# PGTNXEN_cv_out.net
KiCad netlist of a schematic drawn in EAGLE
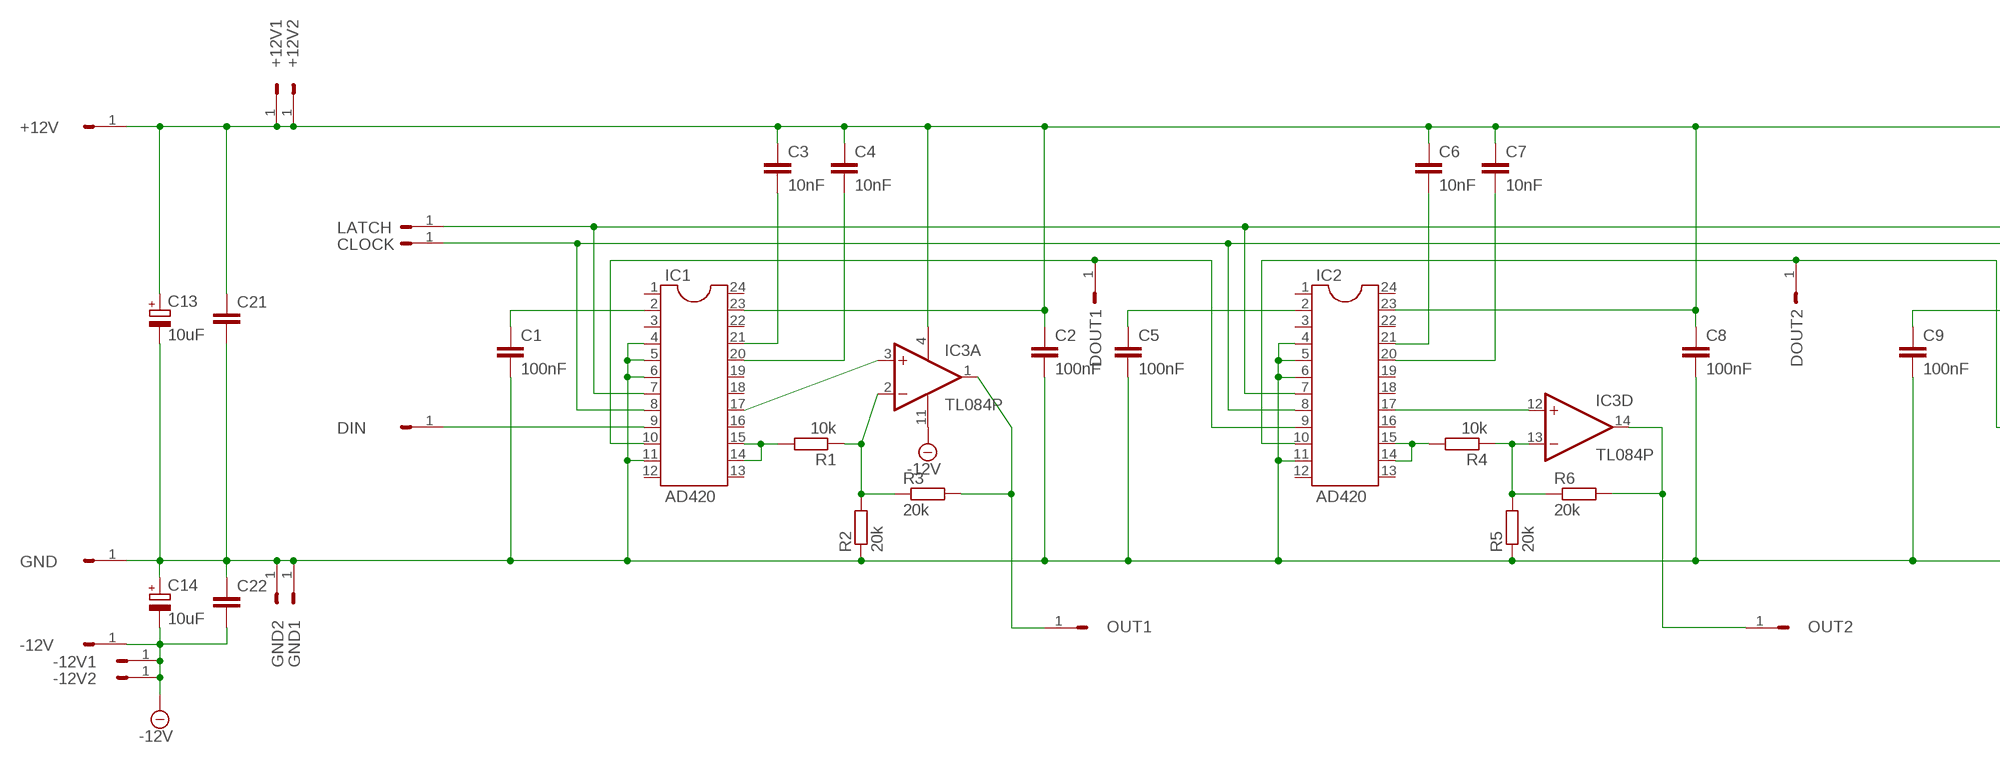
[diagram p0: schematic, sheet 1, part 1 of 2]
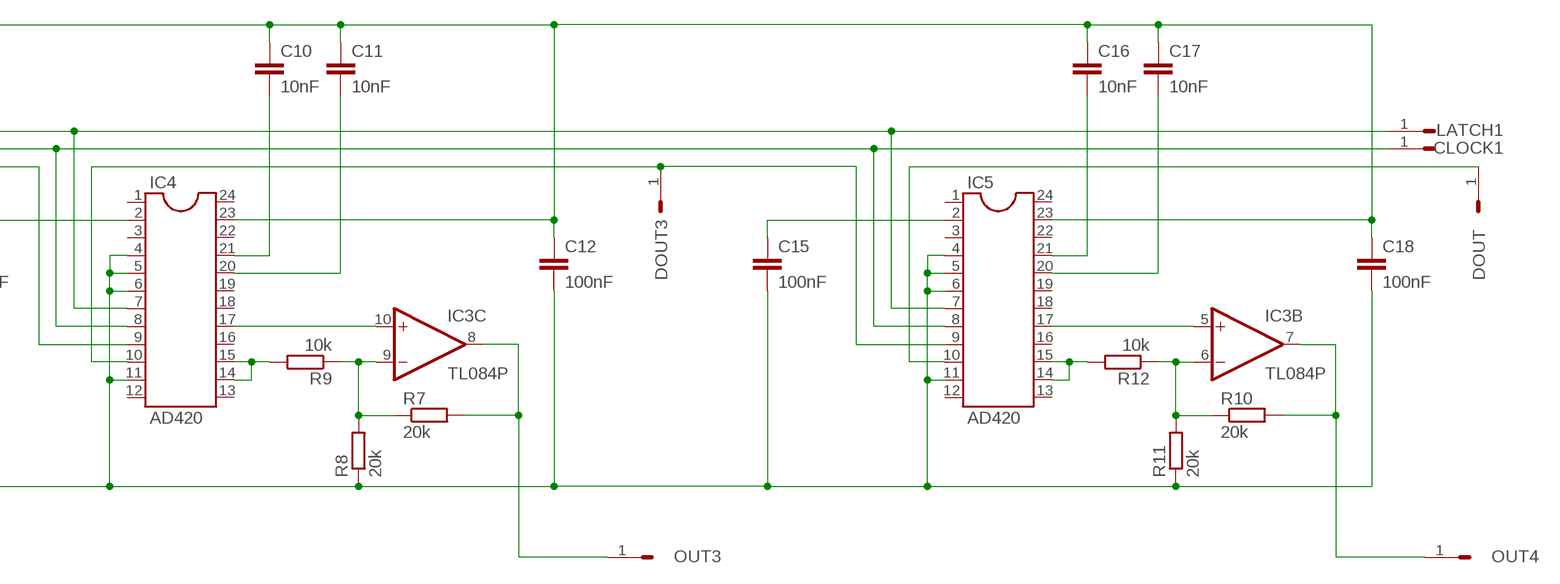
[diagram p1: schematic, sheet 1, part 2 of 2]

(export (version "E")
  (design (tool "Eeschema 10.0.6"))
  (components
    (comp (ref "+12V")
      (value "HEADER/MALE/01")
      (footprint "eagle-import:HEADER_MALE_01")
      (libsource (lib "eagle-import") (part "HEADER/MALE/01"))
    )
    (comp (ref "+12V1")
      (value "HEADER/MALE/01")
      (footprint "eagle-import:HEADER_MALE_01")
      (libsource (lib "eagle-import") (part "HEADER/MALE/01"))
    )
    (comp (ref "+12V2")
      (value "HEADER/MALE/01")
      (footprint "eagle-import:HEADER_MALE_01")
      (libsource (lib "eagle-import") (part "HEADER/MALE/01"))
    )
    (comp (ref "-12V")
      (value "HEADER/MALE/01")
      (footprint "eagle-import:HEADER_MALE_01")
      (libsource (lib "eagle-import") (part "HEADER/MALE/01"))
    )
    (comp (ref "-12V1")
      (value "HEADER/MALE/01")
      (footprint "eagle-import:HEADER_MALE_01")
      (libsource (lib "eagle-import") (part "HEADER/MALE/01"))
    )
    (comp (ref "-12V2")
      (value "HEADER/MALE/01")
      (footprint "eagle-import:HEADER_MALE_01")
      (libsource (lib "eagle-import") (part "HEADER/MALE/01"))
    )
    (comp (ref "C1")
      (value "100nF")
      (footprint "eagle-import:CERAMICDISC_5")
      (libsource (lib "eagle-import") (part "CAPACITORCERAMICDISC/5"))
    )
    (comp (ref "C2")
      (value "100nF")
      (footprint "eagle-import:CERAMICDISC_5")
      (libsource (lib "eagle-import") (part "CAPACITORCERAMICDISC/5"))
    )
    (comp (ref "C3")
      (value "10nF")
      (footprint "eagle-import:CERAMICDISC_5")
      (libsource (lib "eagle-import") (part "CAPACITORCERAMICDISC/5"))
    )
    (comp (ref "C4")
      (value "10nF")
      (footprint "eagle-import:CERAMICDISC_5")
      (libsource (lib "eagle-import") (part "CAPACITORCERAMICDISC/5"))
    )
    (comp (ref "C5")
      (value "100nF")
      (footprint "eagle-import:CERAMICDISC_5")
      (libsource (lib "eagle-import") (part "CAPACITORCERAMICDISC/5"))
    )
    (comp (ref "C6")
      (value "10nF")
      (footprint "eagle-import:CERAMICDISC_5")
      (libsource (lib "eagle-import") (part "CAPACITORCERAMICDISC/5"))
    )
    (comp (ref "C7")
      (value "10nF")
      (footprint "eagle-import:CERAMICDISC_5")
      (libsource (lib "eagle-import") (part "CAPACITORCERAMICDISC/5"))
    )
    (comp (ref "C8")
      (value "100nF")
      (footprint "eagle-import:CERAMICDISC_5")
      (libsource (lib "eagle-import") (part "CAPACITORCERAMICDISC/5"))
    )
    (comp (ref "C9")
      (value "100nF")
      (footprint "eagle-import:CERAMICDISC_5")
      (libsource (lib "eagle-import") (part "CAPACITORCERAMICDISC/5"))
    )
    (comp (ref "C10")
      (value "10nF")
      (footprint "eagle-import:CERAMICDISC_5")
      (libsource (lib "eagle-import") (part "CAPACITORCERAMICDISC/5"))
    )
    (comp (ref "C11")
      (value "10nF")
      (footprint "eagle-import:CERAMICDISC_5")
      (libsource (lib "eagle-import") (part "CAPACITORCERAMICDISC/5"))
    )
    (comp (ref "C12")
      (value "100nF")
      (footprint "eagle-import:CERAMICDISC_5")
      (libsource (lib "eagle-import") (part "CAPACITORCERAMICDISC/5"))
    )
    (comp (ref "C13")
      (value "10uF")
      (footprint "eagle-import:E2,5-6")
      (libsource (lib "eagle-import") (part "CAPACITOR/POLARIZEDE2.5-6"))
    )
    (comp (ref "C14")
      (value "10uF")
      (footprint "eagle-import:E2,5-6")
      (libsource (lib "eagle-import") (part "CAPACITOR/POLARIZEDE2.5-6"))
    )
    (comp (ref "C15")
      (value "100nF")
      (footprint "eagle-import:CERAMICDISC_5")
      (libsource (lib "eagle-import") (part "CAPACITORCERAMICDISC/5"))
    )
    (comp (ref "C16")
      (value "10nF")
      (footprint "eagle-import:CERAMICDISC_5")
      (libsource (lib "eagle-import") (part "CAPACITORCERAMICDISC/5"))
    )
    (comp (ref "C17")
      (value "10nF")
      (footprint "eagle-import:CERAMICDISC_5")
      (libsource (lib "eagle-import") (part "CAPACITORCERAMICDISC/5"))
    )
    (comp (ref "C18")
      (value "100nF")
      (footprint "eagle-import:CERAMICDISC_5")
      (libsource (lib "eagle-import") (part "CAPACITORCERAMICDISC/5"))
    )
    (comp (ref "C21")
      (value "CAPACITORCERAMICDISC/5")
      (footprint "eagle-import:CERAMICDISC_5")
      (libsource (lib "eagle-import") (part "CAPACITORCERAMICDISC/5"))
    )
    (comp (ref "C22")
      (value "CAPACITORCERAMICDISC/5")
      (footprint "eagle-import:CERAMICDISC_5")
      (libsource (lib "eagle-import") (part "CAPACITORCERAMICDISC/5"))
    )
    (comp (ref "CLOCK")
      (value "HEADER/MALE/01")
      (footprint "eagle-import:HEADER_MALE_01")
      (libsource (lib "eagle-import") (part "HEADER/MALE/01"))
    )
    (comp (ref "CLOCK1")
      (value "HEADER/MALE/01")
      (footprint "eagle-import:HEADER_MALE_01")
      (libsource (lib "eagle-import") (part "HEADER/MALE/01"))
    )
    (comp (ref "DIN")
      (value "HEADER/MALE/01")
      (footprint "eagle-import:HEADER_MALE_01")
      (libsource (lib "eagle-import") (part "HEADER/MALE/01"))
    )
    (comp (ref "DOUT")
      (value "HEADER/MALE/01")
      (footprint "eagle-import:HEADER_MALE_01")
      (libsource (lib "eagle-import") (part "HEADER/MALE/01"))
    )
    (comp (ref "DOUT1")
      (value "HEADER/MALE/01")
      (footprint "eagle-import:HEADER_MALE_01")
      (libsource (lib "eagle-import") (part "HEADER/MALE/01"))
    )
    (comp (ref "DOUT2")
      (value "HEADER/MALE/01")
      (footprint "eagle-import:HEADER_MALE_01")
      (libsource (lib "eagle-import") (part "HEADER/MALE/01"))
    )
    (comp (ref "DOUT3")
      (value "HEADER/MALE/01")
      (footprint "eagle-import:HEADER_MALE_01")
      (libsource (lib "eagle-import") (part "HEADER/MALE/01"))
    )
    (comp (ref "GND")
      (value "HEADER/MALE/01")
      (footprint "eagle-import:HEADER_MALE_01")
      (libsource (lib "eagle-import") (part "HEADER/MALE/01"))
    )
    (comp (ref "GND1")
      (value "HEADER/MALE/01")
      (footprint "eagle-import:HEADER_MALE_01")
      (libsource (lib "eagle-import") (part "HEADER/MALE/01"))
    )
    (comp (ref "GND2")
      (value "HEADER/MALE/01")
      (footprint "eagle-import:HEADER_MALE_01")
      (libsource (lib "eagle-import") (part "HEADER/MALE/01"))
    )
    (comp (ref "IC1")
      (value "AD420")
      (footprint "eagle-import:DIL24-3")
      (libsource (lib "eagle-import") (part "DIL24-3"))
    )
    (comp (ref "IC2")
      (value "AD420")
      (footprint "eagle-import:DIL24-3")
      (libsource (lib "eagle-import") (part "DIL24-3"))
    )
    (comp (ref "IC3")
      (value "TL084P")
      (footprint "eagle-import:DIL14")
      (libsource (lib "eagle-import") (part "TL084P"))
    )
    (comp (ref "IC4")
      (value "AD420")
      (footprint "eagle-import:DIL24-3")
      (libsource (lib "eagle-import") (part "DIL24-3"))
    )
    (comp (ref "IC5")
      (value "AD420")
      (footprint "eagle-import:DIL24-3")
      (libsource (lib "eagle-import") (part "DIL24-3"))
    )
    (comp (ref "LATCH")
      (value "HEADER/MALE/01")
      (footprint "eagle-import:HEADER_MALE_01")
      (libsource (lib "eagle-import") (part "HEADER/MALE/01"))
    )
    (comp (ref "LATCH1")
      (value "HEADER/MALE/01")
      (footprint "eagle-import:HEADER_MALE_01")
      (libsource (lib "eagle-import") (part "HEADER/MALE/01"))
    )
    (comp (ref "OUT1")
      (value "HEADER/MALE/01")
      (footprint "eagle-import:HEADER_MALE_01")
      (libsource (lib "eagle-import") (part "HEADER/MALE/01"))
    )
    (comp (ref "OUT2")
      (value "HEADER/MALE/01")
      (footprint "eagle-import:HEADER_MALE_01")
      (libsource (lib "eagle-import") (part "HEADER/MALE/01"))
    )
    (comp (ref "OUT3")
      (value "HEADER/MALE/01")
      (footprint "eagle-import:HEADER_MALE_01")
      (libsource (lib "eagle-import") (part "HEADER/MALE/01"))
    )
    (comp (ref "OUT4")
      (value "HEADER/MALE/01")
      (footprint "eagle-import:HEADER_MALE_01")
      (libsource (lib "eagle-import") (part "HEADER/MALE/01"))
    )
    (comp (ref "R1")
      (value "10k")
      (footprint "eagle-import:0204_7")
      (libsource (lib "eagle-import") (part "R-EU_0204/7"))
    )
    (comp (ref "R2")
      (value "20k")
      (footprint "eagle-import:0204_7")
      (libsource (lib "eagle-import") (part "R-EU_0204/7"))
    )
    (comp (ref "R3")
      (value "20k")
      (footprint "eagle-import:0204_7")
      (libsource (lib "eagle-import") (part "R-EU_0204/7"))
    )
    (comp (ref "R4")
      (value "10k")
      (footprint "eagle-import:0204_7")
      (libsource (lib "eagle-import") (part "R-EU_0204/7"))
    )
    (comp (ref "R5")
      (value "20k")
      (footprint "eagle-import:0204_7")
      (libsource (lib "eagle-import") (part "R-EU_0204/7"))
    )
    (comp (ref "R6")
      (value "20k")
      (footprint "eagle-import:0204_7")
      (libsource (lib "eagle-import") (part "R-EU_0204/7"))
    )
    (comp (ref "R7")
      (value "20k")
      (footprint "eagle-import:0204_7")
      (libsource (lib "eagle-import") (part "R-EU_0204/7"))
    )
    (comp (ref "R8")
      (value "20k")
      (footprint "eagle-import:0204_7")
      (libsource (lib "eagle-import") (part "R-EU_0204/7"))
    )
    (comp (ref "R9")
      (value "10k")
      (footprint "eagle-import:0204_7")
      (libsource (lib "eagle-import") (part "R-EU_0204/7"))
    )
    (comp (ref "R10")
      (value "20k")
      (footprint "eagle-import:0204_7")
      (libsource (lib "eagle-import") (part "R-EU_0204/7"))
    )
    (comp (ref "R11")
      (value "20k")
      (footprint "eagle-import:0204_7")
      (libsource (lib "eagle-import") (part "R-EU_0204/7"))
    )
    (comp (ref "R12")
      (value "10k")
      (footprint "eagle-import:0204_7")
      (libsource (lib "eagle-import") (part "R-EU_0204/7"))
    )
  )
  (nets
    (net (code "1") (name "-12V") (class "Default")
      (node (ref "-12V") (pin "1") (pinfunction "3_1") (pintype "passive"))
      (node (ref "-12V1") (pin "1") (pinfunction "3_1") (pintype "passive"))
      (node (ref "-12V2") (pin "1") (pinfunction "3_1") (pintype "passive"))
      (node (ref "C14") (pin "-") (pinfunction "-_-") (pintype "passive"))
      (node (ref "C22") (pin "2") (pinfunction "2_2") (pintype "passive"))
      (node (ref "IC3") (pin "11") (pinfunction "V-_11") (pintype "power_in"))
    )
    (net (code "2") (name "Net-(+12V-3)") (class "Default")
      (node (ref "+12V") (pin "1") (pinfunction "3_1") (pintype "passive"))
      (node (ref "+12V1") (pin "1") (pinfunction "3_1") (pintype "passive"))
      (node (ref "+12V2") (pin "1") (pinfunction "3_1") (pintype "passive"))
      (node (ref "C10") (pin "1") (pinfunction "1_1") (pintype "passive"))
      (node (ref "C11") (pin "1") (pinfunction "1_1") (pintype "passive"))
      (node (ref "C12") (pin "1") (pinfunction "1_1") (pintype "passive"))
      (node (ref "C13") (pin "+") (pinfunction "+_+") (pintype "passive"))
      (node (ref "C16") (pin "1") (pinfunction "1_1") (pintype "passive"))
      (node (ref "C17") (pin "1") (pinfunction "1_1") (pintype "passive"))
      (node (ref "C18") (pin "1") (pinfunction "1_1") (pintype "passive"))
      (node (ref "C2") (pin "1") (pinfunction "1_1") (pintype "passive"))
      (node (ref "C21") (pin "1") (pinfunction "1_1") (pintype "passive"))
      (node (ref "C3") (pin "1") (pinfunction "1_1") (pintype "passive"))
      (node (ref "C4") (pin "1") (pinfunction "1_1") (pintype "passive"))
      (node (ref "C6") (pin "1") (pinfunction "1_1") (pintype "passive"))
      (node (ref "C7") (pin "1") (pinfunction "1_1") (pintype "passive"))
      (node (ref "C8") (pin "1") (pinfunction "1_1") (pintype "passive"))
      (node (ref "IC1") (pin "23") (pinfunction "23_23") (pintype "passive"))
      (node (ref "IC2") (pin "23") (pinfunction "23_23") (pintype "passive"))
      (node (ref "IC3") (pin "4") (pinfunction "V+_4") (pintype "power_in"))
      (node (ref "IC4") (pin "23") (pinfunction "23_23") (pintype "passive"))
      (node (ref "IC5") (pin "23") (pinfunction "23_23") (pintype "passive"))
    )
    (net (code "3") (name "Net-(C1-Pad1)") (class "Default")
      (node (ref "C1") (pin "1") (pinfunction "1_1") (pintype "passive"))
      (node (ref "IC1") (pin "2") (pinfunction "2_2") (pintype "passive"))
    )
    (net (code "4") (name "Net-(C3-Pad2)") (class "Default")
      (node (ref "C3") (pin "2") (pinfunction "2_2") (pintype "passive"))
      (node (ref "IC1") (pin "21") (pinfunction "21_21") (pintype "passive"))
    )
    (net (code "5") (name "Net-(C4-Pad2)") (class "Default")
      (node (ref "C4") (pin "2") (pinfunction "2_2") (pintype "passive"))
      (node (ref "IC1") (pin "20") (pinfunction "20_20") (pintype "passive"))
    )
    (net (code "6") (name "Net-(C5-Pad1)") (class "Default")
      (node (ref "C5") (pin "1") (pinfunction "1_1") (pintype "passive"))
      (node (ref "IC2") (pin "2") (pinfunction "2_2") (pintype "passive"))
    )
    (net (code "7") (name "Net-(C6-Pad2)") (class "Default")
      (node (ref "C6") (pin "2") (pinfunction "2_2") (pintype "passive"))
      (node (ref "IC2") (pin "21") (pinfunction "21_21") (pintype "passive"))
    )
    (net (code "8") (name "Net-(C7-Pad2)") (class "Default")
      (node (ref "C7") (pin "2") (pinfunction "2_2") (pintype "passive"))
      (node (ref "IC2") (pin "20") (pinfunction "20_20") (pintype "passive"))
    )
    (net (code "9") (name "Net-(C9-Pad1)") (class "Default")
      (node (ref "C9") (pin "1") (pinfunction "1_1") (pintype "passive"))
      (node (ref "IC4") (pin "2") (pinfunction "2_2") (pintype "passive"))
    )
    (net (code "10") (name "Net-(C10-Pad2)") (class "Default")
      (node (ref "C10") (pin "2") (pinfunction "2_2") (pintype "passive"))
      (node (ref "IC4") (pin "21") (pinfunction "21_21") (pintype "passive"))
    )
    (net (code "11") (name "Net-(C11-Pad2)") (class "Default")
      (node (ref "C11") (pin "2") (pinfunction "2_2") (pintype "passive"))
      (node (ref "IC4") (pin "20") (pinfunction "20_20") (pintype "passive"))
    )
    (net (code "12") (name "Net-(C15-Pad1)") (class "Default")
      (node (ref "C15") (pin "1") (pinfunction "1_1") (pintype "passive"))
      (node (ref "IC5") (pin "2") (pinfunction "2_2") (pintype "passive"))
    )
    (net (code "13") (name "Net-(C16-Pad2)") (class "Default")
      (node (ref "C16") (pin "2") (pinfunction "2_2") (pintype "passive"))
      (node (ref "IC5") (pin "21") (pinfunction "21_21") (pintype "passive"))
    )
    (net (code "14") (name "Net-(C17-Pad2)") (class "Default")
      (node (ref "C17") (pin "2") (pinfunction "2_2") (pintype "passive"))
      (node (ref "IC5") (pin "20") (pinfunction "20_20") (pintype "passive"))
    )
    (net (code "15") (name "Net-(CLOCK-3)") (class "Default")
      (node (ref "CLOCK") (pin "1") (pinfunction "3_1") (pintype "passive"))
      (node (ref "CLOCK1") (pin "1") (pinfunction "3_1") (pintype "passive"))
      (node (ref "IC1") (pin "8") (pinfunction "8_8") (pintype "passive"))
      (node (ref "IC2") (pin "8") (pinfunction "8_8") (pintype "passive"))
      (node (ref "IC4") (pin "8") (pinfunction "8_8") (pintype "passive"))
      (node (ref "IC5") (pin "8") (pinfunction "8_8") (pintype "passive"))
    )
    (net (code "16") (name "Net-(DIN-3)") (class "Default")
      (node (ref "DIN") (pin "1") (pinfunction "3_1") (pintype "passive"))
      (node (ref "IC1") (pin "9") (pinfunction "9_9") (pintype "passive"))
    )
    (net (code "17") (name "Net-(DOUT-3)") (class "Default")
      (node (ref "DOUT") (pin "1") (pinfunction "3_1") (pintype "passive"))
      (node (ref "IC5") (pin "10") (pinfunction "10_10") (pintype "passive"))
    )
    (net (code "18") (name "Net-(DOUT1-3)") (class "Default")
      (node (ref "DOUT1") (pin "1") (pinfunction "3_1") (pintype "passive"))
      (node (ref "IC1") (pin "10") (pinfunction "10_10") (pintype "passive"))
      (node (ref "IC2") (pin "9") (pinfunction "9_9") (pintype "passive"))
    )
    (net (code "19") (name "Net-(DOUT2-3)") (class "Default")
      (node (ref "DOUT2") (pin "1") (pinfunction "3_1") (pintype "passive"))
      (node (ref "IC2") (pin "10") (pinfunction "10_10") (pintype "passive"))
      (node (ref "IC4") (pin "9") (pinfunction "9_9") (pintype "passive"))
    )
    (net (code "20") (name "Net-(DOUT3-3)") (class "Default")
      (node (ref "DOUT3") (pin "1") (pinfunction "3_1") (pintype "passive"))
      (node (ref "IC4") (pin "10") (pinfunction "10_10") (pintype "passive"))
      (node (ref "IC5") (pin "9") (pinfunction "9_9") (pintype "passive"))
    )
    (net (code "21") (name "Net-(GND-3)") (class "Default")
      (node (ref "C1") (pin "2") (pinfunction "2_2") (pintype "passive"))
      (node (ref "C12") (pin "2") (pinfunction "2_2") (pintype "passive"))
      (node (ref "C13") (pin "-") (pinfunction "-_-") (pintype "passive"))
      (node (ref "C14") (pin "+") (pinfunction "+_+") (pintype "passive"))
      (node (ref "C15") (pin "2") (pinfunction "2_2") (pintype "passive"))
      (node (ref "C18") (pin "2") (pinfunction "2_2") (pintype "passive"))
      (node (ref "C2") (pin "2") (pinfunction "2_2") (pintype "passive"))
      (node (ref "C21") (pin "2") (pinfunction "2_2") (pintype "passive"))
      (node (ref "C22") (pin "1") (pinfunction "1_1") (pintype "passive"))
      (node (ref "C5") (pin "2") (pinfunction "2_2") (pintype "passive"))
      (node (ref "C8") (pin "2") (pinfunction "2_2") (pintype "passive"))
      (node (ref "C9") (pin "2") (pinfunction "2_2") (pintype "passive"))
      (node (ref "GND") (pin "1") (pinfunction "3_1") (pintype "passive"))
      (node (ref "GND1") (pin "1") (pinfunction "3_1") (pintype "passive"))
      (node (ref "GND2") (pin "1") (pinfunction "3_1") (pintype "passive"))
      (node (ref "IC1") (pin "11") (pinfunction "11_11") (pintype "passive"))
      (node (ref "IC1") (pin "4") (pinfunction "4_4") (pintype "passive"))
      (node (ref "IC1") (pin "5") (pinfunction "5_5") (pintype "passive"))
      (node (ref "IC1") (pin "6") (pinfunction "6_6") (pintype "passive"))
      (node (ref "IC2") (pin "11") (pinfunction "11_11") (pintype "passive"))
      (node (ref "IC2") (pin "4") (pinfunction "4_4") (pintype "passive"))
      (node (ref "IC2") (pin "5") (pinfunction "5_5") (pintype "passive"))
      (node (ref "IC2") (pin "6") (pinfunction "6_6") (pintype "passive"))
      (node (ref "IC4") (pin "11") (pinfunction "11_11") (pintype "passive"))
      (node (ref "IC4") (pin "4") (pinfunction "4_4") (pintype "passive"))
      (node (ref "IC4") (pin "5") (pinfunction "5_5") (pintype "passive"))
      (node (ref "IC4") (pin "6") (pinfunction "6_6") (pintype "passive"))
      (node (ref "IC5") (pin "11") (pinfunction "11_11") (pintype "passive"))
      (node (ref "IC5") (pin "4") (pinfunction "4_4") (pintype "passive"))
      (node (ref "IC5") (pin "5") (pinfunction "5_5") (pintype "passive"))
      (node (ref "IC5") (pin "6") (pinfunction "6_6") (pintype "passive"))
      (node (ref "R11") (pin "1") (pinfunction "1_1") (pintype "passive"))
      (node (ref "R2") (pin "1") (pinfunction "1_1") (pintype "passive"))
      (node (ref "R5") (pin "1") (pinfunction "1_1") (pintype "passive"))
      (node (ref "R8") (pin "1") (pinfunction "1_1") (pintype "passive"))
    )
    (net (code "22") (name "Net-(IC1-Pad14)") (class "Default")
      (node (ref "IC1") (pin "14") (pinfunction "14_14") (pintype "passive"))
      (node (ref "IC1") (pin "15") (pinfunction "15_15") (pintype "passive"))
      (node (ref "R1") (pin "2") (pinfunction "2_2") (pintype "passive"))
    )
    (net (code "23") (name "Net-(IC2-Pad14)") (class "Default")
      (node (ref "IC2") (pin "14") (pinfunction "14_14") (pintype "passive"))
      (node (ref "IC2") (pin "15") (pinfunction "15_15") (pintype "passive"))
      (node (ref "R4") (pin "2") (pinfunction "2_2") (pintype "passive"))
    )
    (net (code "24") (name "Net-(IC3A-+IN)") (class "Default")
      (node (ref "IC1") (pin "17") (pinfunction "17_17") (pintype "passive"))
      (node (ref "IC3") (pin "3") (pinfunction "+IN_3") (pintype "input"))
    )
    (net (code "25") (name "Net-(IC3A--IN)") (class "Default")
      (node (ref "IC3") (pin "2") (pinfunction "-IN_2") (pintype "input"))
      (node (ref "R1") (pin "1") (pinfunction "1_1") (pintype "passive"))
      (node (ref "R2") (pin "2") (pinfunction "2_2") (pintype "passive"))
      (node (ref "R3") (pin "1") (pinfunction "1_1") (pintype "passive"))
    )
    (net (code "26") (name "Net-(IC3A-OUT)") (class "Default")
      (node (ref "IC3") (pin "1") (pinfunction "OUT_1") (pintype "output"))
      (node (ref "OUT1") (pin "1") (pinfunction "3_1") (pintype "passive"))
      (node (ref "R3") (pin "2") (pinfunction "2_2") (pintype "passive"))
    )
    (net (code "27") (name "Net-(IC3B-+IN)") (class "Default")
      (node (ref "IC3") (pin "5") (pinfunction "+IN_5") (pintype "input"))
      (node (ref "IC5") (pin "17") (pinfunction "17_17") (pintype "passive"))
    )
    (net (code "28") (name "Net-(IC3B--IN)") (class "Default")
      (node (ref "IC3") (pin "6") (pinfunction "-IN_6") (pintype "input"))
      (node (ref "R10") (pin "1") (pinfunction "1_1") (pintype "passive"))
      (node (ref "R11") (pin "2") (pinfunction "2_2") (pintype "passive"))
      (node (ref "R12") (pin "1") (pinfunction "1_1") (pintype "passive"))
    )
    (net (code "29") (name "Net-(IC3B-OUT)") (class "Default")
      (node (ref "IC3") (pin "7") (pinfunction "OUT_7") (pintype "output"))
      (node (ref "OUT4") (pin "1") (pinfunction "3_1") (pintype "passive"))
      (node (ref "R10") (pin "2") (pinfunction "2_2") (pintype "passive"))
    )
    (net (code "30") (name "Net-(IC3C-+IN)") (class "Default")
      (node (ref "IC3") (pin "10") (pinfunction "+IN_10") (pintype "input"))
      (node (ref "IC4") (pin "17") (pinfunction "17_17") (pintype "passive"))
    )
    (net (code "31") (name "Net-(IC3C--IN)") (class "Default")
      (node (ref "IC3") (pin "9") (pinfunction "-IN_9") (pintype "input"))
      (node (ref "R7") (pin "1") (pinfunction "1_1") (pintype "passive"))
      (node (ref "R8") (pin "2") (pinfunction "2_2") (pintype "passive"))
      (node (ref "R9") (pin "1") (pinfunction "1_1") (pintype "passive"))
    )
    (net (code "32") (name "Net-(IC3C-OUT)") (class "Default")
      (node (ref "IC3") (pin "8") (pinfunction "OUT_8") (pintype "output"))
      (node (ref "OUT3") (pin "1") (pinfunction "3_1") (pintype "passive"))
      (node (ref "R7") (pin "2") (pinfunction "2_2") (pintype "passive"))
    )
    (net (code "33") (name "Net-(IC3D-+IN)") (class "Default")
      (node (ref "IC2") (pin "17") (pinfunction "17_17") (pintype "passive"))
      (node (ref "IC3") (pin "12") (pinfunction "+IN_12") (pintype "input"))
    )
    (net (code "34") (name "Net-(IC3D--IN)") (class "Default")
      (node (ref "IC3") (pin "13") (pinfunction "-IN_13") (pintype "input"))
      (node (ref "R4") (pin "1") (pinfunction "1_1") (pintype "passive"))
      (node (ref "R5") (pin "2") (pinfunction "2_2") (pintype "passive"))
      (node (ref "R6") (pin "1") (pinfunction "1_1") (pintype "passive"))
    )
    (net (code "35") (name "Net-(IC3D-OUT)") (class "Default")
      (node (ref "IC3") (pin "14") (pinfunction "OUT_14") (pintype "output"))
      (node (ref "OUT2") (pin "1") (pinfunction "3_1") (pintype "passive"))
      (node (ref "R6") (pin "2") (pinfunction "2_2") (pintype "passive"))
    )
    (net (code "36") (name "Net-(IC4-Pad14)") (class "Default")
      (node (ref "IC4") (pin "14") (pinfunction "14_14") (pintype "passive"))
      (node (ref "IC4") (pin "15") (pinfunction "15_15") (pintype "passive"))
      (node (ref "R9") (pin "2") (pinfunction "2_2") (pintype "passive"))
    )
    (net (code "37") (name "Net-(IC5-Pad14)") (class "Default")
      (node (ref "IC5") (pin "14") (pinfunction "14_14") (pintype "passive"))
      (node (ref "IC5") (pin "15") (pinfunction "15_15") (pintype "passive"))
      (node (ref "R12") (pin "2") (pinfunction "2_2") (pintype "passive"))
    )
    (net (code "38") (name "Net-(LATCH-3)") (class "Default")
      (node (ref "IC1") (pin "7") (pinfunction "7_7") (pintype "passive"))
      (node (ref "IC2") (pin "7") (pinfunction "7_7") (pintype "passive"))
      (node (ref "IC4") (pin "7") (pinfunction "7_7") (pintype "passive"))
      (node (ref "IC5") (pin "7") (pinfunction "7_7") (pintype "passive"))
      (node (ref "LATCH") (pin "1") (pinfunction "3_1") (pintype "passive"))
      (node (ref "LATCH1") (pin "1") (pinfunction "3_1") (pintype "passive"))
    )
    (net (code "39") (name "unconnected-(IC1-Pad1)") (class "Default")
      (node (ref "IC1") (pin "1") (pinfunction "1_1") (pintype "passive"))
    )
    (net (code "40") (name "unconnected-(IC1-Pad3)") (class "Default")
      (node (ref "IC1") (pin "3") (pinfunction "3_3") (pintype "passive"))
    )
    (net (code "41") (name "unconnected-(IC1-Pad12)") (class "Default")
      (node (ref "IC1") (pin "12") (pinfunction "12_12") (pintype "passive"))
    )
    (net (code "42") (name "unconnected-(IC1-Pad13)") (class "Default")
      (node (ref "IC1") (pin "13") (pinfunction "13_13") (pintype "passive"))
    )
    (net (code "43") (name "unconnected-(IC1-Pad16)") (class "Default")
      (node (ref "IC1") (pin "16") (pinfunction "16_16") (pintype "passive"))
    )
    (net (code "44") (name "unconnected-(IC1-Pad18)") (class "Default")
      (node (ref "IC1") (pin "18") (pinfunction "18_18") (pintype "passive"))
    )
    (net (code "45") (name "unconnected-(IC1-Pad19)") (class "Default")
      (node (ref "IC1") (pin "19") (pinfunction "19_19") (pintype "passive"))
    )
    (net (code "46") (name "unconnected-(IC1-Pad22)") (class "Default")
      (node (ref "IC1") (pin "22") (pinfunction "22_22") (pintype "passive"))
    )
    (net (code "47") (name "unconnected-(IC1-Pad24)") (class "Default")
      (node (ref "IC1") (pin "24") (pinfunction "24_24") (pintype "passive"))
    )
    (net (code "48") (name "unconnected-(IC2-Pad1)") (class "Default")
      (node (ref "IC2") (pin "1") (pinfunction "1_1") (pintype "passive"))
    )
    (net (code "49") (name "unconnected-(IC2-Pad3)") (class "Default")
      (node (ref "IC2") (pin "3") (pinfunction "3_3") (pintype "passive"))
    )
    (net (code "50") (name "unconnected-(IC2-Pad12)") (class "Default")
      (node (ref "IC2") (pin "12") (pinfunction "12_12") (pintype "passive"))
    )
    (net (code "51") (name "unconnected-(IC2-Pad13)") (class "Default")
      (node (ref "IC2") (pin "13") (pinfunction "13_13") (pintype "passive"))
    )
    (net (code "52") (name "unconnected-(IC2-Pad16)") (class "Default")
      (node (ref "IC2") (pin "16") (pinfunction "16_16") (pintype "passive"))
    )
    (net (code "53") (name "unconnected-(IC2-Pad18)") (class "Default")
      (node (ref "IC2") (pin "18") (pinfunction "18_18") (pintype "passive"))
    )
    (net (code "54") (name "unconnected-(IC2-Pad19)") (class "Default")
      (node (ref "IC2") (pin "19") (pinfunction "19_19") (pintype "passive"))
    )
    (net (code "55") (name "unconnected-(IC2-Pad22)") (class "Default")
      (node (ref "IC2") (pin "22") (pinfunction "22_22") (pintype "passive"))
    )
    (net (code "56") (name "unconnected-(IC2-Pad24)") (class "Default")
      (node (ref "IC2") (pin "24") (pinfunction "24_24") (pintype "passive"))
    )
    (net (code "57") (name "unconnected-(IC4-Pad1)") (class "Default")
      (node (ref "IC4") (pin "1") (pinfunction "1_1") (pintype "passive"))
    )
    (net (code "58") (name "unconnected-(IC4-Pad3)") (class "Default")
      (node (ref "IC4") (pin "3") (pinfunction "3_3") (pintype "passive"))
    )
    (net (code "59") (name "unconnected-(IC4-Pad12)") (class "Default")
      (node (ref "IC4") (pin "12") (pinfunction "12_12") (pintype "passive"))
    )
    (net (code "60") (name "unconnected-(IC4-Pad13)") (class "Default")
      (node (ref "IC4") (pin "13") (pinfunction "13_13") (pintype "passive"))
    )
    (net (code "61") (name "unconnected-(IC4-Pad16)") (class "Default")
      (node (ref "IC4") (pin "16") (pinfunction "16_16") (pintype "passive"))
    )
    (net (code "62") (name "unconnected-(IC4-Pad18)") (class "Default")
      (node (ref "IC4") (pin "18") (pinfunction "18_18") (pintype "passive"))
    )
    (net (code "63") (name "unconnected-(IC4-Pad19)") (class "Default")
      (node (ref "IC4") (pin "19") (pinfunction "19_19") (pintype "passive"))
    )
    (net (code "64") (name "unconnected-(IC4-Pad22)") (class "Default")
      (node (ref "IC4") (pin "22") (pinfunction "22_22") (pintype "passive"))
    )
    (net (code "65") (name "unconnected-(IC4-Pad24)") (class "Default")
      (node (ref "IC4") (pin "24") (pinfunction "24_24") (pintype "passive"))
    )
    (net (code "66") (name "unconnected-(IC5-Pad1)") (class "Default")
      (node (ref "IC5") (pin "1") (pinfunction "1_1") (pintype "passive"))
    )
    (net (code "67") (name "unconnected-(IC5-Pad3)") (class "Default")
      (node (ref "IC5") (pin "3") (pinfunction "3_3") (pintype "passive"))
    )
    (net (code "68") (name "unconnected-(IC5-Pad12)") (class "Default")
      (node (ref "IC5") (pin "12") (pinfunction "12_12") (pintype "passive"))
    )
    (net (code "69") (name "unconnected-(IC5-Pad13)") (class "Default")
      (node (ref "IC5") (pin "13") (pinfunction "13_13") (pintype "passive"))
    )
    (net (code "70") (name "unconnected-(IC5-Pad16)") (class "Default")
      (node (ref "IC5") (pin "16") (pinfunction "16_16") (pintype "passive"))
    )
    (net (code "71") (name "unconnected-(IC5-Pad18)") (class "Default")
      (node (ref "IC5") (pin "18") (pinfunction "18_18") (pintype "passive"))
    )
    (net (code "72") (name "unconnected-(IC5-Pad19)") (class "Default")
      (node (ref "IC5") (pin "19") (pinfunction "19_19") (pintype "passive"))
    )
    (net (code "73") (name "unconnected-(IC5-Pad22)") (class "Default")
      (node (ref "IC5") (pin "22") (pinfunction "22_22") (pintype "passive"))
    )
    (net (code "74") (name "unconnected-(IC5-Pad24)") (class "Default")
      (node (ref "IC5") (pin "24") (pinfunction "24_24") (pintype "passive"))
    )
  )
)
